# PowerSwitch.net
KiCad netlist of a schematic drawn in Altium Designer
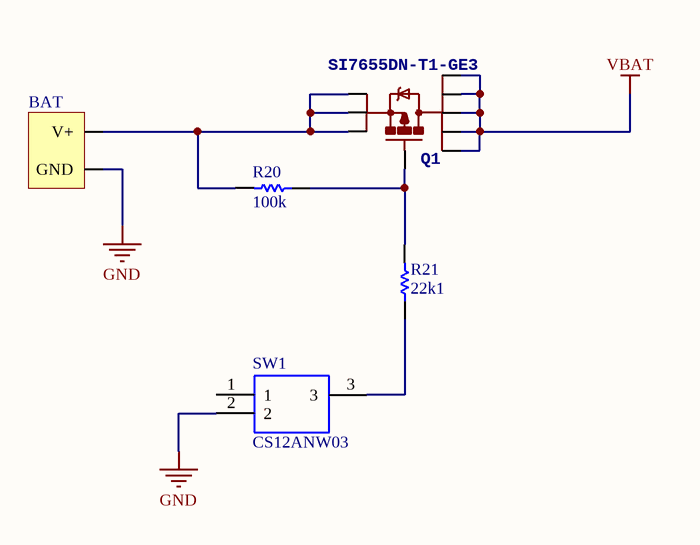
[diagram p0: PowerSwitch.SchDoc]

(export (version "E")
  (design (tool "Eeschema 10.0.6"))
  (components
    (comp (ref "BAT")
      (value "XT60")
      (footprint "BATTERY_CONECTO-PCB")
      (description "XT60 PRT-10474")
      (libsource (lib "Schlib1") (part "BATTERY_CONNECTOR"))
    )
    (comp (ref "Q1")
      (value "SI7655DN-T1-GE3")
      (footprint "PcbLib1:SON8")
      (description "MOSFET P-CH 20V D-S PPAK 1212")
      (libsource (lib "Schlib1") (part "SI7655DN-T1-GE3-3"))
    )
    (comp (ref "R20")
      (value "100k")
      (footprint "0402")
      (description "Resistor")
      (fields (field (name "PUBLISHER") "Altium Limited"))
      (libsource (lib "Miscellaneous Devices") (part "Res1"))
    )
    (comp (ref "R21")
      (value "22k1")
      (footprint "0402")
      (description "Resistor")
      (fields (field (name "PUBLISHER") "Altium Limited"))
      (libsource (lib "Miscellaneous Devices") (part "Res1"))
    )
    (comp (ref "SW1")
      (value "CS12ANW03")
      (footprint "PcbLib1:CS12ANW03")
      (description "NKK SWITCHES - CS12ANW03 - SWITCH, SLIDE, SPDT, 3A, 250V, TH")
      (fields (field (name "RS PART NUMBER") "1251847"))
      (libsource (lib "Schlib1") (part "CS12ANW03"))
    )
  )
  (nets
    (net (code "1") (name "GND") (class "Default")
      (node (ref "BAT") (pin "1") (pinfunction "GND_1") (pintype "passive"))
      (node (ref "SW1") (pin "2") (pinfunction "2_2") (pintype "passive"))
    )
    (net (code "2") (name "Net-(BAT-V+)") (class "Default")
      (node (ref "BAT") (pin "0") (pinfunction "V+_0") (pintype "passive"))
      (node (ref "Q1") (pin "1") (pinfunction "S_1") (pintype "passive"))
      (node (ref "Q1") (pin "2") (pinfunction "S_2") (pintype "passive"))
      (node (ref "Q1") (pin "3") (pinfunction "S_3") (pintype "passive"))
      (node (ref "R20") (pin "2") (pinfunction "2_2") (pintype "passive"))
    )
    (net (code "3") (name "Net-(Q1-G)") (class "Default")
      (node (ref "Q1") (pin "4") (pinfunction "G_4") (pintype "passive"))
      (node (ref "R20") (pin "1") (pinfunction "1_1") (pintype "passive"))
      (node (ref "R21") (pin "2") (pinfunction "2_2") (pintype "passive"))
    )
    (net (code "4") (name "Net-(R21-Pad1)") (class "Default")
      (node (ref "R21") (pin "1") (pinfunction "1_1") (pintype "passive"))
      (node (ref "SW1") (pin "3") (pinfunction "3_3") (pintype "passive"))
    )
    (net (code "5") (name "VBAT") (class "Default")
      (node (ref "Q1") (pin "5") (pinfunction "D_5") (pintype "passive"))
      (node (ref "Q1") (pin "6") (pinfunction "D_6") (pintype "passive"))
      (node (ref "Q1") (pin "7") (pinfunction "D_7") (pintype "passive"))
      (node (ref "Q1") (pin "8") (pinfunction "D_8") (pintype "passive"))
      (node (ref "Q1") (pin "9") (pinfunction "D_9") (pintype "passive"))
    )
    (net (code "6") (name "unconnected-(SW1-Pad1)") (class "Default")
      (node (ref "SW1") (pin "1") (pinfunction "1_1") (pintype "passive"))
    )
  )
)
